# audio.net
KiCad netlist of a schematic drawn in Altium Designer
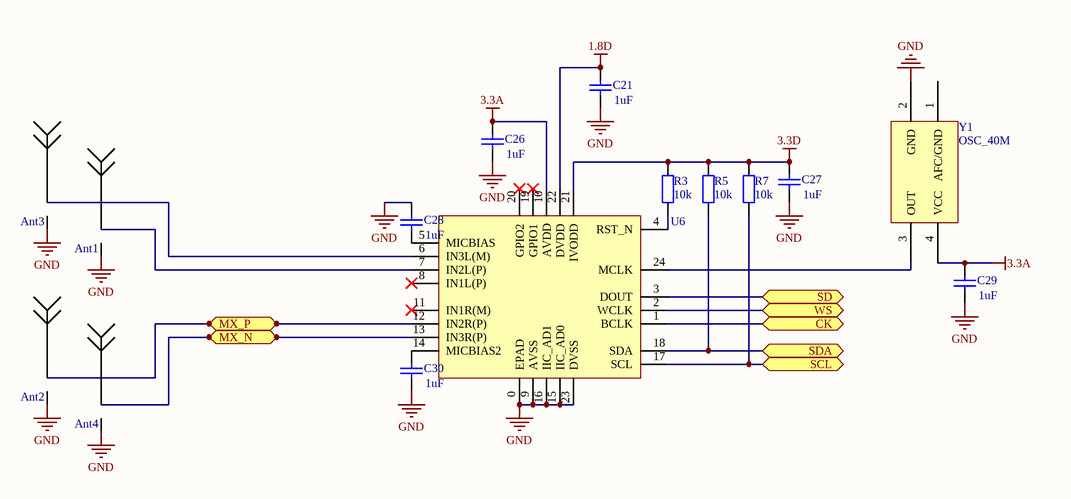
[diagram p0: audio.SchDoc]

(export (version "E")
  (design (tool "Eeschema 10.0.6"))
  (components
    (comp (ref "Ant1") (value "Antenna") (footprint "BK5811:SMA") (libsource (lib "F4SDR") (part "Antenna")))
    (comp (ref "Ant2") (value "Antenna") (footprint "BK5811:SMA") (libsource (lib "F4SDR") (part "Antenna")))
    (comp (ref "Ant3") (value "Antenna") (footprint "BK5811:SMA") (libsource (lib "F4SDR") (part "Antenna")))
    (comp (ref "Ant4") (value "Antenna") (footprint "BK5811:SMA") (libsource (lib "F4SDR") (part "Antenna")))
    (comp (ref "C21")
      (value "1uF")
      (footprint "0402")
      (description "Capacitor")
      (libsource (lib "RTC6705") (part "Cap"))
    )
    (comp (ref "C26")
      (value "1uF")
      (footprint "0402")
      (description "Capacitor")
      (libsource (lib "RTC6705") (part "Cap"))
    )
    (comp (ref "C27")
      (value "1uF")
      (footprint "0402")
      (description "Capacitor")
      (libsource (lib "RTC6705") (part "Cap"))
    )
    (comp (ref "C28")
      (value "1uF")
      (footprint "0402")
      (description "Capacitor")
      (libsource (lib "RTC6705") (part "Cap"))
    )
    (comp (ref "C29")
      (value "1uF")
      (footprint "0402")
      (description "Capacitor")
      (libsource (lib "RTC6705") (part "Cap"))
    )
    (comp (ref "C30")
      (value "1uF")
      (footprint "0402")
      (description "Capacitor")
      (libsource (lib "RTC6705") (part "Cap"))
    )
    (comp (ref "R3")
      (value "10k")
      (footprint "0402")
      (description "Resistor")
      (fields (field (name "Comment") "Res2") (field (name "PUBLISHER") "Altium Limited"))
      (libsource (lib "RTC6705") (part "Res2"))
    )
    (comp (ref "R5")
      (value "10k")
      (footprint "0402")
      (description "Resistor")
      (fields (field (name "Comment") "Res2") (field (name "PUBLISHER") "Altium Limited"))
      (libsource (lib "RTC6705") (part "Res2"))
    )
    (comp (ref "R7")
      (value "10k")
      (footprint "0402")
      (description "Resistor")
      (fields (field (name "Comment") "Res2") (field (name "PUBLISHER") "Altium Limited"))
      (libsource (lib "RTC6705") (part "Res2"))
    )
    (comp (ref "U6")
      (value "TLV320ADC3101")
      (footprint "TLV320ADC3101")
      (libsource (lib "ADAU1761") (part "TLV320ADC3101"))
    )
    (comp (ref "Y1") (value "OSC_40M") (footprint "TXC_7Q") (libsource (lib "F4SDR") (part "OSC_40M")))
  )
  (nets
    (net (code "1") (name "/CK") (class "Default")
      (node (ref "U6") (pin "1") (pinfunction "BCLK_1") (pintype "passive"))
    )
    (net (code "2") (name "/MX_N") (class "Default")
      (node (ref "Ant4") (pin "1") (pinfunction "1_1") (pintype "passive"))
      (node (ref "U6") (pin "13") (pinfunction "IN3R(P)_13") (pintype "passive"))
    )
    (net (code "3") (name "/MX_P") (class "Default")
      (node (ref "Ant2") (pin "1") (pinfunction "1_1") (pintype "passive"))
      (node (ref "U6") (pin "12") (pinfunction "IN2R(P)_12") (pintype "passive"))
    )
    (net (code "4") (name "/SCL") (class "Default")
      (node (ref "R7") (pin "1") (pinfunction "1_1") (pintype "passive"))
      (node (ref "U6") (pin "17") (pinfunction "SCL_17") (pintype "passive"))
    )
    (net (code "5") (name "/SD") (class "Default")
      (node (ref "U6") (pin "3") (pinfunction "DOUT_3") (pintype "passive"))
    )
    (net (code "6") (name "/SDA") (class "Default")
      (node (ref "R5") (pin "1") (pinfunction "1_1") (pintype "passive"))
      (node (ref "U6") (pin "18") (pinfunction "SDA_18") (pintype "passive"))
    )
    (net (code "7") (name "/WS") (class "Default")
      (node (ref "U6") (pin "2") (pinfunction "WCLK_2") (pintype "passive"))
    )
    (net (code "8") (name "1.8D") (class "Default")
      (node (ref "C21") (pin "2") (pinfunction "2_2") (pintype "passive"))
      (node (ref "U6") (pin "22") (pinfunction "DVDD_22") (pintype "passive"))
    )
    (net (code "9") (name "3.3A") (class "Default")
      (node (ref "C26") (pin "2") (pinfunction "2_2") (pintype "passive"))
      (node (ref "C29") (pin "2") (pinfunction "2_2") (pintype "passive"))
      (node (ref "U6") (pin "10") (pinfunction "AVDD_10") (pintype "passive"))
      (node (ref "Y1") (pin "4") (pinfunction "VCC_4") (pintype "passive"))
    )
    (net (code "10") (name "3.3D") (class "Default")
      (node (ref "C27") (pin "2") (pinfunction "2_2") (pintype "passive"))
      (node (ref "R3") (pin "2") (pinfunction "2_2") (pintype "passive"))
      (node (ref "R5") (pin "2") (pinfunction "2_2") (pintype "passive"))
      (node (ref "R7") (pin "2") (pinfunction "2_2") (pintype "passive"))
      (node (ref "U6") (pin "21") (pinfunction "IVODD_21") (pintype "passive"))
    )
    (net (code "11") (name "GND") (class "Default")
      (node (ref "Ant1") (pin "GND") (pinfunction "G_GND") (pintype "passive"))
      (node (ref "Ant2") (pin "GND") (pinfunction "G_GND") (pintype "passive"))
      (node (ref "Ant3") (pin "GND") (pinfunction "G_GND") (pintype "passive"))
      (node (ref "Ant4") (pin "GND") (pinfunction "G_GND") (pintype "passive"))
      (node (ref "C21") (pin "1") (pinfunction "1_1") (pintype "passive"))
      (node (ref "C26") (pin "1") (pinfunction "1_1") (pintype "passive"))
      (node (ref "C27") (pin "1") (pinfunction "1_1") (pintype "passive"))
      (node (ref "C28") (pin "2") (pinfunction "2_2") (pintype "passive"))
      (node (ref "C29") (pin "1") (pinfunction "1_1") (pintype "passive"))
      (node (ref "C30") (pin "1") (pinfunction "1_1") (pintype "passive"))
      (node (ref "U6") (pin "0") (pinfunction "EPAD_0") (pintype "passive"))
      (node (ref "U6") (pin "15") (pinfunction "IIC_AD0_15") (pintype "passive"))
      (node (ref "U6") (pin "16") (pinfunction "IIC_AD1_16") (pintype "passive"))
      (node (ref "U6") (pin "23") (pinfunction "DVSS_23") (pintype "passive"))
      (node (ref "U6") (pin "9") (pinfunction "AVSS_9") (pintype "passive"))
      (node (ref "Y1") (pin "2") (pinfunction "GND_2") (pintype "passive"))
    )
    (net (code "12") (name "Net-(U6-IN2L(P))") (class "Default")
      (node (ref "Ant1") (pin "1") (pinfunction "1_1") (pintype "passive"))
      (node (ref "U6") (pin "7") (pinfunction "IN2L(P)_7") (pintype "passive"))
    )
    (net (code "13") (name "Net-(U6-IN3L(M))") (class "Default")
      (node (ref "Ant3") (pin "1") (pinfunction "1_1") (pintype "passive"))
      (node (ref "U6") (pin "6") (pinfunction "IN3L(M)_6") (pintype "passive"))
    )
    (net (code "14") (name "Net-(U6-MCLK)") (class "Default")
      (node (ref "U6") (pin "24") (pinfunction "MCLK_24") (pintype "passive"))
      (node (ref "Y1") (pin "3") (pinfunction "OUT_3") (pintype "passive"))
    )
    (net (code "15") (name "Net-(U6-MICBIAS)") (class "Default")
      (node (ref "C28") (pin "1") (pinfunction "1_1") (pintype "passive"))
      (node (ref "U6") (pin "5") (pinfunction "MICBIAS_5") (pintype "passive"))
    )
    (net (code "16") (name "Net-(U6-MICBIAS2)") (class "Default")
      (node (ref "C30") (pin "2") (pinfunction "2_2") (pintype "passive"))
      (node (ref "U6") (pin "14") (pinfunction "MICBIAS2_14") (pintype "passive"))
    )
    (net (code "17") (name "Net-(U6-RST_N)") (class "Default")
      (node (ref "R3") (pin "1") (pinfunction "1_1") (pintype "passive"))
      (node (ref "U6") (pin "4") (pinfunction "RST_N_4") (pintype "passive"))
    )
    (net (code "18") (name "unconnected-(U6-GPIO1-Pad19)") (class "Default")
      (node (ref "U6") (pin "19") (pinfunction "GPIO1_19") (pintype "passive+no_connect"))
    )
    (net (code "19") (name "unconnected-(U6-GPIO2-Pad20)") (class "Default")
      (node (ref "U6") (pin "20") (pinfunction "GPIO2_20") (pintype "passive+no_connect"))
    )
    (net (code "20") (name "unconnected-(U6-IN1L(P)-Pad8)") (class "Default")
      (node (ref "U6") (pin "8") (pinfunction "IN1L(P)_8") (pintype "passive+no_connect"))
    )
    (net (code "21") (name "unconnected-(U6-IN1R(M)-Pad11)") (class "Default")
      (node (ref "U6") (pin "11") (pinfunction "IN1R(M)_11") (pintype "passive+no_connect"))
    )
    (net (code "22") (name "unconnected-(Y1-AFC{slash}GND-Pad1)") (class "Default")
      (node (ref "Y1") (pin "1") (pinfunction "AFC/GND_1") (pintype "passive"))
    )
  )
)
